# 4_-GPS_SIM_SSD.net
KiCad netlist of a schematic drawn in Altium Designer
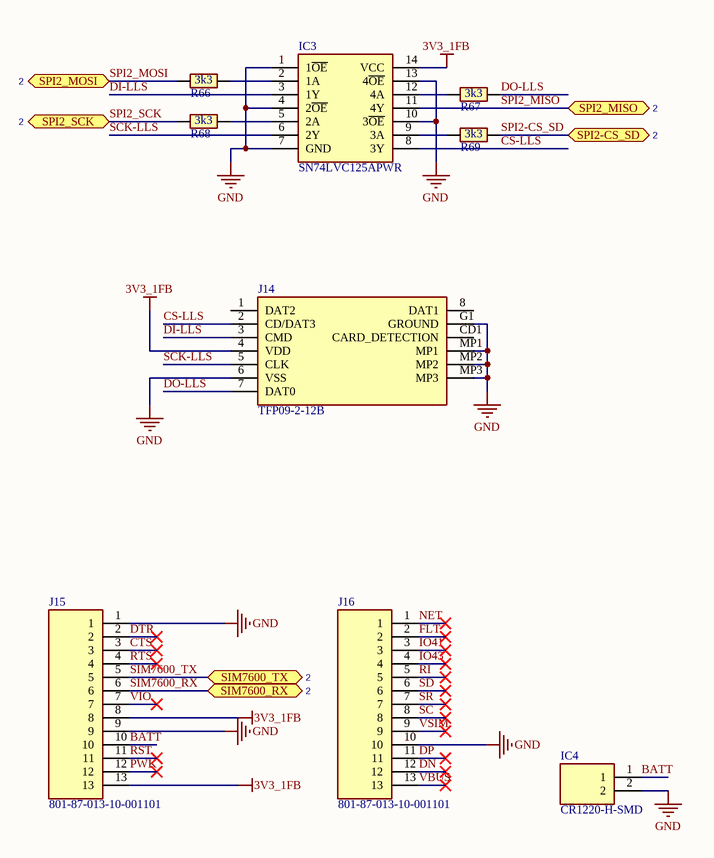
[diagram p0: [4]-GPS_SIM_SSD.SchDoc]

(export (version "E")
  (design (tool "Eeschema 10.0.6"))
  (components
    (comp (ref "IC3")
      (value "SN74LVC125APWR")
      (footprint "SN74LVC125APWR")
      (description "Integrated Circuit")
      (fields (field (name "MOUSER PART NUMBER") "595-SN74LVC125APWR"))
      (libsource (lib "SamacSys") (part "SN74LVC125APWR"))
    )
    (comp (ref "IC4")
      (value "CR1220-H-SMD")
      (footprint "CR1220HSMD")
      (description "Integrated Circuit")
      (libsource (lib "SamacSys") (part "CR1220-H-SMD"))
    )
    (comp (ref "J14")
      (value "TFP09-2-12B")
      (footprint "TFP09212B")
      (description "Connector")
      (libsource (lib "SamacSys") (part "TFP09-2-12B"))
    )
    (comp (ref "J15")
      (value "801-87-013-10-001101")
      (footprint "RHDR13W60P0X254_1X13_3302X254X700P")
      (description "WR-PHD Socket Header, THT, Vertical, pitch 2.54mm, 1 Row, 13P")
      (fields (field (name "MOUSER PART NUMBER") "437-8018701310001101"))
      (libsource (lib "SamacSys") (part "801-87-013-10-001101"))
    )
    (comp (ref "J16")
      (value "801-87-013-10-001101")
      (footprint "RHDR13W60P0X254_1X13_3302X254X700P")
      (description "WR-PHD Socket Header, THT, Vertical, pitch 2.54mm, 1 Row, 13P")
      (fields (field (name "MOUSER PART NUMBER") "437-8018701310001101"))
      (libsource (lib "SamacSys") (part "801-87-013-10-001101"))
    )
    (comp (ref "R66")
      (value "R0603_3k3")
      (footprint "RES-SMD-0603")
      (description "Resistor")
      (fields
        (field (name "MANUFACTURER_PART_NUMBER") "ERJ-3EKF3301V")
        (field (name "MOUSER PART NUMBER") "667-ERJ-3EKF3301V")
      )
      (libsource (lib "SamacSys") (part "R0603_3k3"))
    )
    (comp (ref "R67")
      (value "R0603_3k3")
      (footprint "RES-SMD-0603")
      (description "Resistor")
      (fields
        (field (name "MANUFACTURER_PART_NUMBER") "ERJ-3EKF3301V")
        (field (name "MOUSER PART NUMBER") "667-ERJ-3EKF3301V")
      )
      (libsource (lib "SamacSys") (part "R0603_3k3"))
    )
    (comp (ref "R68")
      (value "R0603_3k3")
      (footprint "RES-SMD-0603")
      (description "Resistor")
      (fields
        (field (name "MANUFACTURER_PART_NUMBER") "ERJ-3EKF3301V")
        (field (name "MOUSER PART NUMBER") "667-ERJ-3EKF3301V")
      )
      (libsource (lib "SamacSys") (part "R0603_3k3"))
    )
    (comp (ref "R69")
      (value "R0603_3k3")
      (footprint "RES-SMD-0603")
      (description "Resistor")
      (fields
        (field (name "MANUFACTURER_PART_NUMBER") "ERJ-3EKF3301V")
        (field (name "MOUSER PART NUMBER") "667-ERJ-3EKF3301V")
      )
      (libsource (lib "SamacSys") (part "R0603_3k3"))
    )
  )
  (nets
    (net (code "1") (name "/BATT") (class "Default")
      (node (ref "IC4") (pin "1") (pinfunction "1_1") (pintype "passive"))
      (node (ref "J15") (pin "10") (pinfunction "10_10") (pintype "passive"))
    )
    (net (code "2") (name "/CS-LLS") (class "Default")
      (node (ref "IC3") (pin "8") (pinfunction "3Y_8") (pintype "passive"))
      (node (ref "J14") (pin "2") (pinfunction "CD/DAT3_2") (pintype "passive"))
    )
    (net (code "3") (name "/CTS") (class "Default")
      (node (ref "J15") (pin "3") (pinfunction "3_3") (pintype "passive+no_connect"))
    )
    (net (code "4") (name "/DI-LLS") (class "Default")
      (node (ref "IC3") (pin "3") (pinfunction "1Y_3") (pintype "passive"))
      (node (ref "J14") (pin "3") (pinfunction "CMD_3") (pintype "passive"))
    )
    (net (code "5") (name "/DN") (class "Default")
      (node (ref "J16") (pin "12") (pinfunction "12_12") (pintype "passive+no_connect"))
    )
    (net (code "6") (name "/DO-LLS") (class "Default")
      (node (ref "J14") (pin "7") (pinfunction "DAT0_7") (pintype "passive"))
      (node (ref "R67") (pin "2") (pinfunction "2_2") (pintype "passive"))
    )
    (net (code "7") (name "/DP") (class "Default")
      (node (ref "J16") (pin "11") (pinfunction "11_11") (pintype "passive+no_connect"))
    )
    (net (code "8") (name "/DTR") (class "Default")
      (node (ref "J15") (pin "2") (pinfunction "2_2") (pintype "passive+no_connect"))
    )
    (net (code "9") (name "/FLT") (class "Default")
      (node (ref "J16") (pin "2") (pinfunction "2_2") (pintype "passive+no_connect"))
    )
    (net (code "10") (name "/IO41") (class "Default")
      (node (ref "J16") (pin "3") (pinfunction "3_3") (pintype "passive+no_connect"))
    )
    (net (code "11") (name "/IO43") (class "Default")
      (node (ref "J16") (pin "4") (pinfunction "4_4") (pintype "passive+no_connect"))
    )
    (net (code "12") (name "/NET") (class "Default")
      (node (ref "J16") (pin "1") (pinfunction "1_1") (pintype "passive+no_connect"))
    )
    (net (code "13") (name "/PWK") (class "Default")
      (node (ref "J15") (pin "12") (pinfunction "12_12") (pintype "passive+no_connect"))
    )
    (net (code "14") (name "/RI") (class "Default")
      (node (ref "J16") (pin "5") (pinfunction "5_5") (pintype "passive+no_connect"))
    )
    (net (code "15") (name "/RST") (class "Default")
      (node (ref "J15") (pin "11") (pinfunction "11_11") (pintype "passive+no_connect"))
    )
    (net (code "16") (name "/RTS") (class "Default")
      (node (ref "J15") (pin "4") (pinfunction "4_4") (pintype "passive+no_connect"))
    )
    (net (code "17") (name "/SC") (class "Default")
      (node (ref "J16") (pin "8") (pinfunction "8_8") (pintype "passive+no_connect"))
    )
    (net (code "18") (name "/SCK-LLS") (class "Default")
      (node (ref "IC3") (pin "6") (pinfunction "2Y_6") (pintype "passive"))
      (node (ref "J14") (pin "5") (pinfunction "CLK_5") (pintype "passive"))
    )
    (net (code "19") (name "/SD") (class "Default")
      (node (ref "J16") (pin "6") (pinfunction "6_6") (pintype "passive+no_connect"))
    )
    (net (code "20") (name "/SIM7600_RX") (class "Default")
      (node (ref "J15") (pin "6") (pinfunction "6_6") (pintype "passive"))
    )
    (net (code "21") (name "/SIM7600_TX") (class "Default")
      (node (ref "J15") (pin "5") (pinfunction "5_5") (pintype "passive"))
    )
    (net (code "22") (name "/SPI2-CS_SD") (class "Default")
      (node (ref "R69") (pin "2") (pinfunction "2_2") (pintype "passive"))
    )
    (net (code "23") (name "/SPI2_MISO") (class "Default")
      (node (ref "IC3") (pin "11") (pinfunction "4Y_11") (pintype "passive"))
    )
    (net (code "24") (name "/SPI2_MOSI") (class "Default")
      (node (ref "R66") (pin "1") (pinfunction "1_1") (pintype "passive"))
    )
    (net (code "25") (name "/SPI2_SCK") (class "Default")
      (node (ref "R68") (pin "1") (pinfunction "1_1") (pintype "passive"))
    )
    (net (code "26") (name "/SR") (class "Default")
      (node (ref "J16") (pin "7") (pinfunction "7_7") (pintype "passive+no_connect"))
    )
    (net (code "27") (name "/VBUS") (class "Default")
      (node (ref "J16") (pin "13") (pinfunction "13_13") (pintype "passive+no_connect"))
    )
    (net (code "28") (name "/VIO") (class "Default")
      (node (ref "J15") (pin "7") (pinfunction "7_7") (pintype "passive+no_connect"))
    )
    (net (code "29") (name "/VSIM") (class "Default")
      (node (ref "J16") (pin "9") (pinfunction "9_9") (pintype "passive+no_connect"))
    )
    (net (code "30") (name "3V3_1FB") (class "Default")
      (node (ref "IC3") (pin "14") (pinfunction "VCC_14") (pintype "passive"))
      (node (ref "J14") (pin "4") (pinfunction "VDD_4") (pintype "passive"))
      (node (ref "J15") (pin "13") (pinfunction "13_13") (pintype "passive"))
      (node (ref "J15") (pin "8") (pinfunction "8_8") (pintype "passive"))
    )
    (net (code "31") (name "GND") (class "Default")
      (node (ref "IC3") (pin "1") (pinfunction "1~{OE}_1") (pintype "passive"))
      (node (ref "IC3") (pin "10") (pinfunction "3~{OE}_10") (pintype "passive"))
      (node (ref "IC3") (pin "13") (pinfunction "4~{OE}_13") (pintype "passive"))
      (node (ref "IC3") (pin "4") (pinfunction "2~{OE}_4") (pintype "passive"))
      (node (ref "IC3") (pin "7") (pinfunction "GND_7") (pintype "passive"))
      (node (ref "IC4") (pin "2") (pinfunction "2_2") (pintype "passive"))
      (node (ref "J14") (pin "6") (pinfunction "VSS_6") (pintype "passive"))
      (node (ref "J14") (pin "G1") (pinfunction "GROUND_G1") (pintype "passive"))
      (node (ref "J14") (pin "MP1") (pinfunction "MP1_MP1") (pintype "passive"))
      (node (ref "J14") (pin "MP2") (pinfunction "MP2_MP2") (pintype "passive"))
      (node (ref "J14") (pin "MP3") (pinfunction "MP3_MP3") (pintype "passive"))
      (node (ref "J15") (pin "1") (pinfunction "1_1") (pintype "passive"))
      (node (ref "J15") (pin "9") (pinfunction "9_9") (pintype "passive"))
      (node (ref "J16") (pin "10") (pinfunction "10_10") (pintype "passive"))
    )
    (net (code "32") (name "Net-(IC3-1A)") (class "Default")
      (node (ref "IC3") (pin "2") (pinfunction "1A_2") (pintype "passive"))
      (node (ref "R66") (pin "2") (pinfunction "2_2") (pintype "passive"))
    )
    (net (code "33") (name "Net-(IC3-2A)") (class "Default")
      (node (ref "IC3") (pin "5") (pinfunction "2A_5") (pintype "passive"))
      (node (ref "R68") (pin "2") (pinfunction "2_2") (pintype "passive"))
    )
    (net (code "34") (name "Net-(IC3-3A)") (class "Default")
      (node (ref "IC3") (pin "9") (pinfunction "3A_9") (pintype "passive"))
      (node (ref "R69") (pin "1") (pinfunction "1_1") (pintype "passive"))
    )
    (net (code "35") (name "Net-(IC3-4A)") (class "Default")
      (node (ref "IC3") (pin "12") (pinfunction "4A_12") (pintype "passive"))
      (node (ref "R67") (pin "1") (pinfunction "1_1") (pintype "passive"))
    )
    (net (code "36") (name "unconnected-(J14-CARD_DETECTION-PadCD1)") (class "Default")
      (node (ref "J14") (pin "CD1") (pinfunction "CARD_DETECTION_CD1") (pintype "passive"))
    )
    (net (code "37") (name "unconnected-(J14-DAT1-Pad8)") (class "Default")
      (node (ref "J14") (pin "8") (pinfunction "DAT1_8") (pintype "passive"))
    )
    (net (code "38") (name "unconnected-(J14-DAT2-Pad1)") (class "Default")
      (node (ref "J14") (pin "1") (pinfunction "DAT2_1") (pintype "passive"))
    )
  )
)
